# BSS_T10_Underboard_component_design.net
KiCad netlist of a schematic drawn in EAGLE
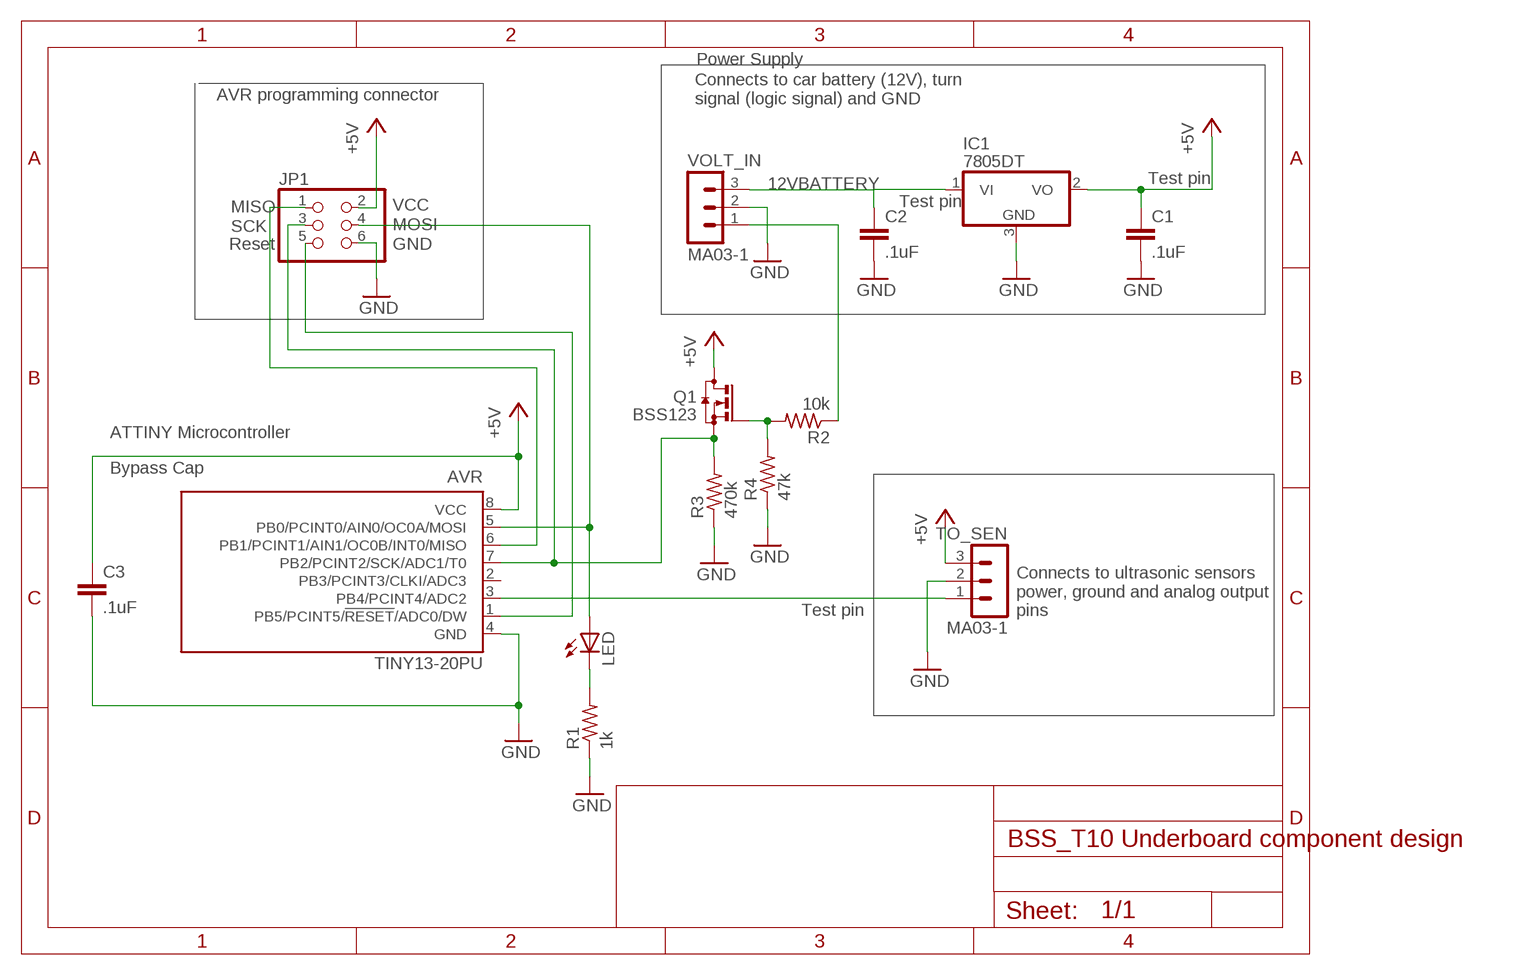
[diagram p0: schematic, sheet 1]

(export (version "E")
  (design (tool "Eeschema 10.0.6"))
  (components
    (comp (ref "AVR")
      (value "TINY13-20PU")
      (footprint "eagle-import:DIL08")
      (fields (field (name "MPN") "ATTINY13-20PU"))
      (libsource (lib "eagle-import") (part "TINY13PU-20"))
    )
    (comp (ref "C1")
      (value ".1uF")
      (footprint "eagle-import:C0805")
      (libsource (lib "eagle-import") (part "C-EUC0805"))
    )
    (comp (ref "C2")
      (value ".1uF")
      (footprint "eagle-import:C0805")
      (libsource (lib "eagle-import") (part "C-EUC0805"))
    )
    (comp (ref "C3")
      (value ".1uF")
      (footprint "eagle-import:C0805")
      (libsource (lib "eagle-import") (part "C-EUC0805"))
    )
    (comp (ref "IC1")
      (value "7805DT")
      (footprint "eagle-import:TO252")
      (libsource (lib "eagle-import") (part "78DT05"))
    )
    (comp (ref "JP1")
      (value "PINHD-2X3")
      (footprint "eagle-import:2X03")
      (libsource (lib "eagle-import") (part "PINHD-2X3"))
    )
    (comp (ref "LED")
      (value "LED5MM")
      (footprint "eagle-import:LED5MM")
      (libsource (lib "eagle-import") (part "LED5MM"))
    )
    (comp (ref "Q1")
      (value "BSS123")
      (footprint "eagle-import:SOT23")
      (libsource (lib "eagle-import") (part "BSS123"))
    )
    (comp (ref "R1")
      (value "1k")
      (footprint "eagle-import:R0805")
      (libsource (lib "eagle-import") (part "R-US_R0805"))
    )
    (comp (ref "R2")
      (value "10k")
      (footprint "eagle-import:R0805")
      (libsource (lib "eagle-import") (part "R-US_R0805"))
    )
    (comp (ref "R3")
      (value "470k")
      (footprint "eagle-import:R0805")
      (libsource (lib "eagle-import") (part "R-US_R0805"))
    )
    (comp (ref "R4")
      (value "47k")
      (footprint "eagle-import:R0805")
      (libsource (lib "eagle-import") (part "R-US_R0805"))
    )
    (comp (ref "TO_SEN")
      (value "MA03-1")
      (footprint "eagle-import:MA03-1")
      (libsource (lib "eagle-import") (part "MA03-1"))
    )
    (comp (ref "VOLT_IN")
      (value "MA03-1")
      (footprint "eagle-import:MA03-1")
      (libsource (lib "eagle-import") (part "MA03-1"))
    )
  )
  (nets
    (net (code "1") (name "+5V") (class "Default")
      (node (ref "AVR") (pin "8") (pinfunction "VCC_8") (pintype "power_in"))
      (node (ref "C1") (pin "1") (pinfunction "1_1") (pintype "passive"))
      (node (ref "C3") (pin "1") (pinfunction "1_1") (pintype "passive"))
      (node (ref "IC1") (pin "2") (pinfunction "VO_2") (pintype "passive"))
      (node (ref "JP1") (pin "2") (pinfunction "2_2") (pintype "passive"))
      (node (ref "Q1") (pin "3") (pinfunction "D_3") (pintype "passive"))
      (node (ref "TO_SEN") (pin "3") (pinfunction "3_3") (pintype "passive"))
    )
    (net (code "2") (name "/12VBATTERY") (class "Default")
      (node (ref "C2") (pin "1") (pinfunction "1_1") (pintype "passive"))
      (node (ref "IC1") (pin "1") (pinfunction "VI_1") (pintype "input"))
      (node (ref "VOLT_IN") (pin "3") (pinfunction "3_3") (pintype "passive"))
    )
    (net (code "3") (name "GND") (class "Default")
      (node (ref "AVR") (pin "4") (pinfunction "GND_4") (pintype "power_in"))
      (node (ref "C1") (pin "2") (pinfunction "2_2") (pintype "passive"))
      (node (ref "C2") (pin "2") (pinfunction "2_2") (pintype "passive"))
      (node (ref "C3") (pin "2") (pinfunction "2_2") (pintype "passive"))
      (node (ref "IC1") (pin "3") (pinfunction "GND_3") (pintype "passive"))
      (node (ref "JP1") (pin "6") (pinfunction "6_6") (pintype "passive"))
      (node (ref "R1") (pin "1") (pinfunction "1_1") (pintype "passive"))
      (node (ref "R3") (pin "1") (pinfunction "1_1") (pintype "passive"))
      (node (ref "R4") (pin "1") (pinfunction "1_1") (pintype "passive"))
      (node (ref "TO_SEN") (pin "2") (pinfunction "2_2") (pintype "passive"))
      (node (ref "VOLT_IN") (pin "2") (pinfunction "2_2") (pintype "passive"))
    )
    (net (code "4") (name "Net-(AVR-PB0{slash}PCINT0{slash}AIN0{slash}OC0A{slash}MOSI)") (class "Default")
      (node (ref "AVR") (pin "5") (pinfunction "PB0/PCINT0/AIN0/OC0A/MOSI_5") (pintype "bidirectional"))
      (node (ref "JP1") (pin "4") (pinfunction "4_4") (pintype "passive"))
      (node (ref "LED") (pin "A") (pinfunction "A_A") (pintype "passive"))
    )
    (net (code "5") (name "Net-(AVR-PB1{slash}PCINT1{slash}AIN1{slash}OC0B{slash}INT0{slash}MISO)") (class "Default")
      (node (ref "AVR") (pin "6") (pinfunction "PB1/PCINT1/AIN1/OC0B/INT0/MISO_6") (pintype "bidirectional"))
      (node (ref "JP1") (pin "1") (pinfunction "1_1") (pintype "passive"))
    )
    (net (code "6") (name "Net-(AVR-PB2{slash}PCINT2{slash}SCK{slash}ADC1{slash}T0)") (class "Default")
      (node (ref "AVR") (pin "7") (pinfunction "PB2/PCINT2/SCK/ADC1/T0_7") (pintype "bidirectional"))
      (node (ref "JP1") (pin "3") (pinfunction "3_3") (pintype "passive"))
      (node (ref "Q1") (pin "2") (pinfunction "S_2") (pintype "passive"))
      (node (ref "R3") (pin "2") (pinfunction "2_2") (pintype "passive"))
    )
    (net (code "7") (name "Net-(AVR-PB4{slash}PCINT4{slash}ADC2)") (class "Default")
      (node (ref "AVR") (pin "3") (pinfunction "PB4/PCINT4/ADC2_3") (pintype "bidirectional"))
      (node (ref "TO_SEN") (pin "1") (pinfunction "1_1") (pintype "passive"))
    )
    (net (code "8") (name "Net-(AVR-PB5{slash}PCINT5{slash}~{RESET}{slash}ADC0{slash}DW)") (class "Default")
      (node (ref "AVR") (pin "1") (pinfunction "PB5/PCINT5/~{RESET}/ADC0/DW_1") (pintype "bidirectional"))
      (node (ref "JP1") (pin "5") (pinfunction "5_5") (pintype "passive"))
    )
    (net (code "9") (name "Net-(LED-C)") (class "Default")
      (node (ref "LED") (pin "K") (pinfunction "C_K") (pintype "passive"))
      (node (ref "R1") (pin "2") (pinfunction "2_2") (pintype "passive"))
    )
    (net (code "10") (name "Net-(Q1-G)") (class "Default")
      (node (ref "Q1") (pin "1") (pinfunction "G_1") (pintype "passive"))
      (node (ref "R2") (pin "2") (pinfunction "2_2") (pintype "passive"))
      (node (ref "R4") (pin "2") (pinfunction "2_2") (pintype "passive"))
    )
    (net (code "11") (name "Net-(R2-Pad1)") (class "Default")
      (node (ref "R2") (pin "1") (pinfunction "1_1") (pintype "passive"))
      (node (ref "VOLT_IN") (pin "1") (pinfunction "1_1") (pintype "passive"))
    )
    (net (code "12") (name "unconnected-(AVR-PB3{slash}PCINT3{slash}CLKI{slash}ADC3-Pad2)") (class "Default")
      (node (ref "AVR") (pin "2") (pinfunction "PB3/PCINT3/CLKI/ADC3_2") (pintype "bidirectional"))
    )
  )
)
